# USART_LPUART.net
KiCad netlist of a schematic drawn in Altium Designer
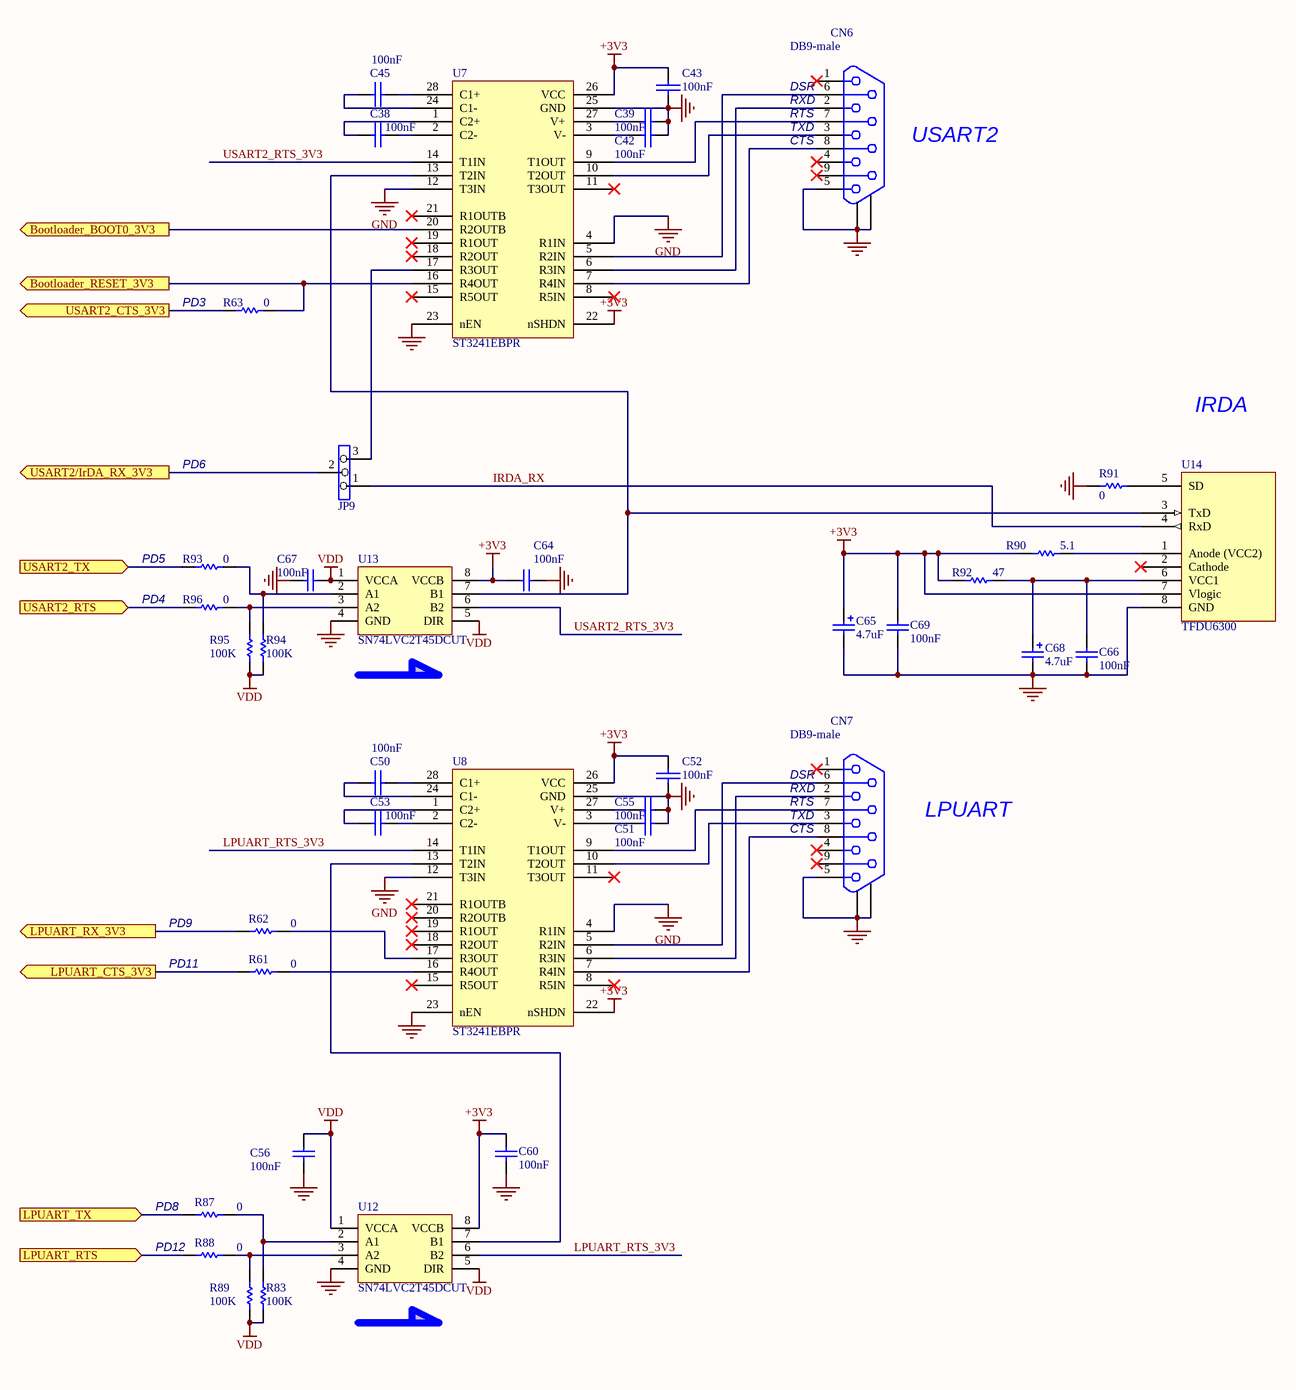
[diagram p0: USART_LPUART.SchDoc]

(export (version "E")
  (design (tool "Eeschema 10.0.6"))
  (components
    (comp (ref "C38")
      (value "100nF")
      (footprint "0402C")
      (description "Capacitor")
      (libsource (lib "*") (part "CAP"))
    )
    (comp (ref "C39")
      (value "100nF")
      (footprint "0402C")
      (description "Capacitor")
      (libsource (lib "*") (part "CAP"))
    )
    (comp (ref "C42")
      (value "100nF")
      (footprint "0402C")
      (description "Capacitor")
      (libsource (lib "*") (part "CAP"))
    )
    (comp (ref "C43")
      (value "100nF")
      (footprint "0402C")
      (description "Capacitor")
      (libsource (lib "*") (part "CAP"))
    )
    (comp (ref "C45")
      (value "100nF")
      (footprint "0402C")
      (description "Capacitor")
      (libsource (lib "*") (part "CAP"))
    )
    (comp (ref "C50")
      (value "100nF")
      (footprint "0402C")
      (description "Capacitor")
      (libsource (lib "*") (part "CAP"))
    )
    (comp (ref "C51")
      (value "100nF")
      (footprint "0402C")
      (description "Capacitor")
      (libsource (lib "*") (part "CAP"))
    )
    (comp (ref "C52")
      (value "100nF")
      (footprint "0402C")
      (description "Capacitor")
      (libsource (lib "*") (part "CAP"))
    )
    (comp (ref "C53")
      (value "100nF")
      (footprint "0402C")
      (description "Capacitor")
      (libsource (lib "*") (part "CAP"))
    )
    (comp (ref "C55")
      (value "100nF")
      (footprint "0402C")
      (description "Capacitor")
      (libsource (lib "*") (part "CAP"))
    )
    (comp (ref "C56")
      (value "100nF")
      (footprint "0402C")
      (description "Capacitor")
      (fields (field (name "PUBLISHER") "Altium Limited"))
      (libsource (lib "Miscellaneous Devices") (part "CAP"))
    )
    (comp (ref "C60")
      (value "100nF")
      (footprint "0402C")
      (description "Capacitor")
      (fields (field (name "PUBLISHER") "Altium Limited"))
      (libsource (lib "Miscellaneous Devices") (part "CAP"))
    )
    (comp (ref "C64")
      (value "100nF")
      (footprint "0402C")
      (description "Capacitor")
      (fields (field (name "PUBLISHER") "Altium Limited"))
      (libsource (lib "Miscellaneous Devices") (part "CAP"))
    )
    (comp (ref "C65")
      (value "4.7uF")
      (footprint "TAN-A")
      (description "Polarized Capacitor (Radial)")
      (fields (field (name "PUBLISHER") "Altium Limited"))
      (libsource (lib "Miscellaneous Devices") (part "Cap Pol1"))
    )
    (comp (ref "C66")
      (value "100nF")
      (footprint "0402C")
      (description "Capacitor")
      (fields (field (name "PUBLISHER") "Altium Limited"))
      (libsource (lib "Miscellaneous Devices") (part "CAP"))
    )
    (comp (ref "C67")
      (value "100nF")
      (footprint "0402C")
      (description "Capacitor")
      (fields (field (name "PUBLISHER") "Altium Limited"))
      (libsource (lib "Miscellaneous Devices") (part "CAP"))
    )
    (comp (ref "C68")
      (value "4.7uF")
      (footprint "TAN-A")
      (description "Polarized Capacitor (Radial)")
      (fields (field (name "PUBLISHER") "Altium Limited"))
      (libsource (lib "Miscellaneous Devices") (part "Cap Pol1"))
    )
    (comp (ref "C69")
      (value "100nF")
      (footprint "0402C")
      (description "Capacitor")
      (fields (field (name "PUBLISHER") "Altium Limited"))
      (libsource (lib "Miscellaneous Devices") (part "CAP"))
    )
    (comp (ref "CN6") (value "DB9-male") (footprint "DB9/M") (libsource (lib "MB1070") (part "DB9")))
    (comp (ref "CN7") (value "DB9-male") (footprint "DB9/M") (libsource (lib "MB1070") (part "DB9")))
    (comp (ref "JP9") (value "~") (footprint "SIP3") (libsource (lib "STR910_SCHLIB") (part "Jumper3")))
    (comp (ref "R61")
      (value "0")
      (footprint "0603R")
      (description "Resistor")
      (fields (field (name "PUBLISHER") "Altium Limited"))
      (libsource (lib "Miscellaneous Devices") (part "Res1"))
    )
    (comp (ref "R62")
      (value "0")
      (footprint "0603R")
      (description "Resistor")
      (fields (field (name "PUBLISHER") "Altium Limited"))
      (libsource (lib "Miscellaneous Devices") (part "Res1"))
    )
    (comp (ref "R63")
      (value "0")
      (footprint "0603R")
      (description "Resistor")
      (fields (field (name "PUBLISHER") "Altium Limited"))
      (libsource (lib "Miscellaneous Devices") (part "Res1"))
    )
    (comp (ref "R83")
      (value "100K")
      (footprint "0402R")
      (description "Resistor")
      (fields (field (name "PUBLISHER") "Altium Limited"))
      (libsource (lib "Miscellaneous Devices") (part "Res1"))
    )
    (comp (ref "R87")
      (value "0")
      (footprint "0603R")
      (description "Resistor")
      (fields (field (name "PUBLISHER") "Altium Limited"))
      (libsource (lib "Miscellaneous Devices") (part "Res1"))
    )
    (comp (ref "R88")
      (value "0")
      (footprint "0603R")
      (description "Resistor")
      (fields (field (name "PUBLISHER") "Altium Limited"))
      (libsource (lib "Miscellaneous Devices") (part "Res1"))
    )
    (comp (ref "R89")
      (value "100K")
      (footprint "0402R")
      (description "Resistor")
      (fields (field (name "PUBLISHER") "Altium Limited"))
      (libsource (lib "Miscellaneous Devices") (part "Res1"))
    )
    (comp (ref "R90")
      (value "5.1")
      (footprint "0402R")
      (description "Resistor")
      (fields (field (name "PUBLISHER") "Altium Limited"))
      (libsource (lib "Miscellaneous Devices") (part "Res1"))
    )
    (comp (ref "R91")
      (value "0")
      (footprint "0603R")
      (description "Resistor")
      (fields (field (name "PUBLISHER") "Altium Limited"))
      (libsource (lib "Miscellaneous Devices") (part "Res1"))
    )
    (comp (ref "R92")
      (value "47")
      (footprint "0402R")
      (description "Resistor")
      (fields (field (name "PUBLISHER") "Altium Limited"))
      (libsource (lib "Miscellaneous Devices") (part "Res1"))
    )
    (comp (ref "R93")
      (value "0")
      (footprint "0603R")
      (description "Resistor")
      (fields (field (name "PUBLISHER") "Altium Limited"))
      (libsource (lib "Miscellaneous Devices") (part "Res1"))
    )
    (comp (ref "R94")
      (value "100K")
      (footprint "0402R")
      (description "Resistor")
      (fields (field (name "PUBLISHER") "Altium Limited"))
      (libsource (lib "Miscellaneous Devices") (part "Res1"))
    )
    (comp (ref "R95")
      (value "100K")
      (footprint "0402R")
      (description "Resistor")
      (fields (field (name "PUBLISHER") "Altium Limited"))
      (libsource (lib "Miscellaneous Devices") (part "Res1"))
    )
    (comp (ref "R96")
      (value "0")
      (footprint "0603R")
      (description "Resistor")
      (fields (field (name "PUBLISHER") "Altium Limited"))
      (libsource (lib "Miscellaneous Devices") (part "Res1"))
    )
    (comp (ref "U7")
      (value "ST3241EBPR")
      (footprint "SSOP28_0R65_10R2X7R8")
      (libsource (lib "*") (part "ST3241"))
    )
    (comp (ref "U8")
      (value "ST3241EBPR")
      (footprint "SSOP28_0R65_10R2X7R8")
      (libsource (lib "*") (part "ST3241"))
    )
    (comp (ref "U12")
      (value "SN74LVC2T45DCUT")
      (footprint "USOP8_0R5_2X3R1")
      (libsource (lib "MB818") (part "SN74LVC2T45DCUT"))
    )
    (comp (ref "U13")
      (value "SN74LVC2T45DCUT")
      (footprint "USOP8_0R5_2X3R1")
      (libsource (lib "MB818") (part "SN74LVC2T45DCUT"))
    )
    (comp (ref "U14")
      (value "TFDU6300")
      (footprint "IR_VISHAY3")
      (description "TFDU4300")
      (libsource (lib "*") (part "TFDU4300"))
    )
  )
  (nets
    (net (code "1") (name "+3V3") (class "Default")
      (node (ref "C43") (pin "2") (pinfunction "2_2") (pintype "passive"))
      (node (ref "C52") (pin "2") (pinfunction "2_2") (pintype "passive"))
      (node (ref "C60") (pin "2") (pinfunction "2_2") (pintype "passive"))
      (node (ref "C64") (pin "2") (pinfunction "2_2") (pintype "passive"))
      (node (ref "C65") (pin "1") (pinfunction "1_1") (pintype "passive"))
      (node (ref "C69") (pin "2") (pinfunction "2_2") (pintype "passive"))
      (node (ref "R90") (pin "1") (pinfunction "1_1") (pintype "passive"))
      (node (ref "R92") (pin "1") (pinfunction "1_1") (pintype "passive"))
      (node (ref "U12") (pin "8") (pinfunction "VCCB_8") (pintype "passive"))
      (node (ref "U13") (pin "8") (pinfunction "VCCB_8") (pintype "passive"))
      (node (ref "U14") (pin "7") (pinfunction "Vlogic_7") (pintype "passive"))
      (node (ref "U7") (pin "22") (pinfunction "nSHDN_22") (pintype "passive"))
      (node (ref "U7") (pin "26") (pinfunction "VCC_26") (pintype "passive"))
      (node (ref "U8") (pin "22") (pinfunction "nSHDN_22") (pintype "passive"))
      (node (ref "U8") (pin "26") (pinfunction "VCC_26") (pintype "passive"))
    )
    (net (code "2") (name "/Bootloader_BOOT0_3V3") (class "Default")
      (node (ref "U7") (pin "20") (pinfunction "R2OUTB_20") (pintype "passive"))
    )
    (net (code "3") (name "/Bootloader_RESET_3V3") (class "Default")
      (node (ref "R63") (pin "1") (pinfunction "1_1") (pintype "passive"))
      (node (ref "U7") (pin "16") (pinfunction "R4OUT_16") (pintype "passive"))
    )
    (net (code "4") (name "/IRDA_RX") (class "Default")
      (node (ref "JP9") (pin "1") (pintype "passive"))
      (node (ref "U14") (pin "4") (pinfunction "RxD_4") (pintype "output"))
    )
    (net (code "5") (name "/LPUART_CTS_3V3") (class "Default")
      (node (ref "R61") (pin "1") (pinfunction "1_1") (pintype "passive"))
    )
    (net (code "6") (name "/LPUART_RTS") (class "Default")
      (node (ref "R88") (pin "1") (pinfunction "1_1") (pintype "passive"))
    )
    (net (code "7") (name "/LPUART_RTS_3V3") (class "Default")
      (node (ref "U12") (pin "6") (pinfunction "B2_6") (pintype "passive"))
      (node (ref "U8") (pin "14") (pinfunction "T1IN_14") (pintype "passive"))
    )
    (net (code "8") (name "/LPUART_RX_3V3") (class "Default")
      (node (ref "R62") (pin "1") (pinfunction "1_1") (pintype "passive"))
    )
    (net (code "9") (name "/LPUART_TX") (class "Default")
      (node (ref "R87") (pin "1") (pinfunction "1_1") (pintype "passive"))
    )
    (net (code "10") (name "/USART2_CTS_3V3") (class "Default")
      (node (ref "R63") (pin "2") (pinfunction "2_2") (pintype "passive"))
    )
    (net (code "11") (name "/USART2_RTS") (class "Default")
      (node (ref "R96") (pin "2") (pinfunction "2_2") (pintype "passive"))
    )
    (net (code "12") (name "/USART2_RTS_3V3") (class "Default")
      (node (ref "U13") (pin "6") (pinfunction "B2_6") (pintype "passive"))
      (node (ref "U7") (pin "14") (pinfunction "T1IN_14") (pintype "passive"))
    )
    (net (code "13") (name "/USART2_TX") (class "Default")
      (node (ref "R93") (pin "2") (pinfunction "2_2") (pintype "passive"))
    )
    (net (code "14") (name "/USART2{slash}IrDA_RX_3V3") (class "Default")
      (node (ref "JP9") (pin "2") (pintype "passive"))
    )
    (net (code "15") (name "GND") (class "Default")
      (node (ref "C39") (pin "2") (pinfunction "2_2") (pintype "passive"))
      (node (ref "C42") (pin "2") (pinfunction "2_2") (pintype "passive"))
      (node (ref "C43") (pin "1") (pinfunction "1_1") (pintype "passive"))
      (node (ref "C51") (pin "2") (pinfunction "2_2") (pintype "passive"))
      (node (ref "C52") (pin "1") (pinfunction "1_1") (pintype "passive"))
      (node (ref "C55") (pin "2") (pinfunction "2_2") (pintype "passive"))
      (node (ref "C56") (pin "1") (pinfunction "1_1") (pintype "passive"))
      (node (ref "C60") (pin "1") (pinfunction "1_1") (pintype "passive"))
      (node (ref "C64") (pin "1") (pinfunction "1_1") (pintype "passive"))
      (node (ref "C65") (pin "2") (pinfunction "2_2") (pintype "passive"))
      (node (ref "C66") (pin "1") (pinfunction "1_1") (pintype "passive"))
      (node (ref "C67") (pin "1") (pinfunction "1_1") (pintype "passive"))
      (node (ref "C68") (pin "2") (pinfunction "2_2") (pintype "passive"))
      (node (ref "C69") (pin "1") (pinfunction "1_1") (pintype "passive"))
      (node (ref "CN6") (pin "10") (pinfunction "10_10") (pintype "passive"))
      (node (ref "CN6") (pin "11") (pinfunction "11_11") (pintype "passive"))
      (node (ref "CN6") (pin "5") (pinfunction "5_5") (pintype "passive"))
      (node (ref "CN7") (pin "10") (pinfunction "10_10") (pintype "passive"))
      (node (ref "CN7") (pin "11") (pinfunction "11_11") (pintype "passive"))
      (node (ref "CN7") (pin "5") (pinfunction "5_5") (pintype "passive"))
      (node (ref "R91") (pin "2") (pinfunction "2_2") (pintype "passive"))
      (node (ref "U12") (pin "4") (pinfunction "GND_4") (pintype "passive"))
      (node (ref "U13") (pin "4") (pinfunction "GND_4") (pintype "passive"))
      (node (ref "U14") (pin "8") (pinfunction "GND_8") (pintype "passive"))
      (node (ref "U7") (pin "12") (pinfunction "T3IN_12") (pintype "passive"))
      (node (ref "U7") (pin "23") (pinfunction "nEN_23") (pintype "passive"))
      (node (ref "U7") (pin "25") (pinfunction "GND_25") (pintype "passive"))
      (node (ref "U7") (pin "4") (pinfunction "R1IN_4") (pintype "passive"))
      (node (ref "U8") (pin "12") (pinfunction "T3IN_12") (pintype "passive"))
      (node (ref "U8") (pin "23") (pinfunction "nEN_23") (pintype "passive"))
      (node (ref "U8") (pin "25") (pinfunction "GND_25") (pintype "passive"))
      (node (ref "U8") (pin "4") (pinfunction "R1IN_4") (pintype "passive"))
    )
    (net (code "16") (name "Net-(U7-C1+)") (class "Default")
      (node (ref "C45") (pin "2") (pinfunction "2_2") (pintype "passive"))
      (node (ref "U7") (pin "28") (pinfunction "C1+_28") (pintype "passive"))
    )
    (net (code "17") (name "Net-(U7-C1-)") (class "Default")
      (node (ref "C45") (pin "1") (pinfunction "1_1") (pintype "passive"))
      (node (ref "U7") (pin "24") (pinfunction "C1-_24") (pintype "passive"))
    )
    (net (code "18") (name "Net-(U7-C2+)") (class "Default")
      (node (ref "C38") (pin "1") (pinfunction "1_1") (pintype "passive"))
      (node (ref "U7") (pin "1") (pinfunction "C2+_1") (pintype "passive"))
    )
    (net (code "19") (name "Net-(U7-C2-)") (class "Default")
      (node (ref "C38") (pin "2") (pinfunction "2_2") (pintype "passive"))
      (node (ref "U7") (pin "2") (pinfunction "C2-_2") (pintype "passive"))
    )
    (net (code "20") (name "Net-(U7-R2IN)") (class "Default")
      (node (ref "CN6") (pin "6") (pinfunction "6_6") (pintype "passive"))
      (node (ref "U7") (pin "5") (pinfunction "R2IN_5") (pintype "passive"))
    )
    (net (code "21") (name "Net-(U7-R3IN)") (class "Default")
      (node (ref "CN6") (pin "2") (pinfunction "2_2") (pintype "passive"))
      (node (ref "U7") (pin "6") (pinfunction "R3IN_6") (pintype "passive"))
    )
    (net (code "22") (name "Net-(U7-R3OUT)") (class "Default")
      (node (ref "JP9") (pin "3") (pintype "passive"))
      (node (ref "U7") (pin "17") (pinfunction "R3OUT_17") (pintype "passive"))
    )
    (net (code "23") (name "Net-(U7-R4IN)") (class "Default")
      (node (ref "CN6") (pin "8") (pinfunction "8_8") (pintype "passive"))
      (node (ref "U7") (pin "7") (pinfunction "R4IN_7") (pintype "passive"))
    )
    (net (code "24") (name "Net-(U7-T1OUT)") (class "Default")
      (node (ref "CN6") (pin "7") (pinfunction "7_7") (pintype "passive"))
      (node (ref "U7") (pin "9") (pinfunction "T1OUT_9") (pintype "passive"))
    )
    (net (code "25") (name "Net-(U7-T2OUT)") (class "Default")
      (node (ref "CN6") (pin "3") (pinfunction "3_3") (pintype "passive"))
      (node (ref "U7") (pin "10") (pinfunction "T2OUT_10") (pintype "passive"))
    )
    (net (code "26") (name "Net-(U7-V+)") (class "Default")
      (node (ref "C39") (pin "1") (pinfunction "1_1") (pintype "passive"))
      (node (ref "U7") (pin "27") (pinfunction "V+_27") (pintype "passive"))
    )
    (net (code "27") (name "Net-(U7-V-)") (class "Default")
      (node (ref "C42") (pin "1") (pinfunction "1_1") (pintype "passive"))
      (node (ref "U7") (pin "3") (pinfunction "V-_3") (pintype "passive"))
    )
    (net (code "28") (name "Net-(U8-C1+)") (class "Default")
      (node (ref "C50") (pin "2") (pinfunction "2_2") (pintype "passive"))
      (node (ref "U8") (pin "28") (pinfunction "C1+_28") (pintype "passive"))
    )
    (net (code "29") (name "Net-(U8-C1-)") (class "Default")
      (node (ref "C50") (pin "1") (pinfunction "1_1") (pintype "passive"))
      (node (ref "U8") (pin "24") (pinfunction "C1-_24") (pintype "passive"))
    )
    (net (code "30") (name "Net-(U8-C2+)") (class "Default")
      (node (ref "C53") (pin "1") (pinfunction "1_1") (pintype "passive"))
      (node (ref "U8") (pin "1") (pinfunction "C2+_1") (pintype "passive"))
    )
    (net (code "31") (name "Net-(U8-C2-)") (class "Default")
      (node (ref "C53") (pin "2") (pinfunction "2_2") (pintype "passive"))
      (node (ref "U8") (pin "2") (pinfunction "C2-_2") (pintype "passive"))
    )
    (net (code "32") (name "Net-(U8-R2IN)") (class "Default")
      (node (ref "CN7") (pin "6") (pinfunction "6_6") (pintype "passive"))
      (node (ref "U8") (pin "5") (pinfunction "R2IN_5") (pintype "passive"))
    )
    (net (code "33") (name "Net-(U8-R3IN)") (class "Default")
      (node (ref "CN7") (pin "2") (pinfunction "2_2") (pintype "passive"))
      (node (ref "U8") (pin "6") (pinfunction "R3IN_6") (pintype "passive"))
    )
    (net (code "34") (name "Net-(U8-R3OUT)") (class "Default")
      (node (ref "R62") (pin "2") (pinfunction "2_2") (pintype "passive"))
      (node (ref "U8") (pin "17") (pinfunction "R3OUT_17") (pintype "passive"))
    )
    (net (code "35") (name "Net-(U8-R4IN)") (class "Default")
      (node (ref "CN7") (pin "8") (pinfunction "8_8") (pintype "passive"))
      (node (ref "U8") (pin "7") (pinfunction "R4IN_7") (pintype "passive"))
    )
    (net (code "36") (name "Net-(U8-R4OUT)") (class "Default")
      (node (ref "R61") (pin "2") (pinfunction "2_2") (pintype "passive"))
      (node (ref "U8") (pin "16") (pinfunction "R4OUT_16") (pintype "passive"))
    )
    (net (code "37") (name "Net-(U8-T1OUT)") (class "Default")
      (node (ref "CN7") (pin "7") (pinfunction "7_7") (pintype "passive"))
      (node (ref "U8") (pin "9") (pinfunction "T1OUT_9") (pintype "passive"))
    )
    (net (code "38") (name "Net-(U8-T2OUT)") (class "Default")
      (node (ref "CN7") (pin "3") (pinfunction "3_3") (pintype "passive"))
      (node (ref "U8") (pin "10") (pinfunction "T2OUT_10") (pintype "passive"))
    )
    (net (code "39") (name "Net-(U8-V+)") (class "Default")
      (node (ref "C55") (pin "1") (pinfunction "1_1") (pintype "passive"))
      (node (ref "U8") (pin "27") (pinfunction "V+_27") (pintype "passive"))
    )
    (net (code "40") (name "Net-(U8-V-)") (class "Default")
      (node (ref "C51") (pin "1") (pinfunction "1_1") (pintype "passive"))
      (node (ref "U8") (pin "3") (pinfunction "V-_3") (pintype "passive"))
    )
    (net (code "41") (name "Net-(U12-A1)") (class "Default")
      (node (ref "R83") (pin "1") (pinfunction "1_1") (pintype "passive"))
      (node (ref "R87") (pin "2") (pinfunction "2_2") (pintype "passive"))
      (node (ref "U12") (pin "2") (pinfunction "A1_2") (pintype "passive"))
    )
    (net (code "42") (name "Net-(U12-A2)") (class "Default")
      (node (ref "R88") (pin "2") (pinfunction "2_2") (pintype "passive"))
      (node (ref "R89") (pin "1") (pinfunction "1_1") (pintype "passive"))
      (node (ref "U12") (pin "3") (pinfunction "A2_3") (pintype "passive"))
    )
    (net (code "43") (name "Net-(U12-B1)") (class "Default")
      (node (ref "U12") (pin "7") (pinfunction "B1_7") (pintype "passive"))
      (node (ref "U8") (pin "13") (pinfunction "T2IN_13") (pintype "passive"))
    )
    (net (code "44") (name "Net-(U13-A1)") (class "Default")
      (node (ref "R93") (pin "1") (pinfunction "1_1") (pintype "passive"))
      (node (ref "R94") (pin "1") (pinfunction "1_1") (pintype "passive"))
      (node (ref "U13") (pin "2") (pinfunction "A1_2") (pintype "passive"))
    )
    (net (code "45") (name "Net-(U13-A2)") (class "Default")
      (node (ref "R95") (pin "1") (pinfunction "1_1") (pintype "passive"))
      (node (ref "R96") (pin "1") (pinfunction "1_1") (pintype "passive"))
      (node (ref "U13") (pin "3") (pinfunction "A2_3") (pintype "passive"))
    )
    (net (code "46") (name "Net-(U13-B1)") (class "Default")
      (node (ref "U13") (pin "7") (pinfunction "B1_7") (pintype "passive"))
      (node (ref "U14") (pin "3") (pinfunction "TxD_3") (pintype "input"))
      (node (ref "U7") (pin "13") (pinfunction "T2IN_13") (pintype "passive"))
    )
    (net (code "47") (name "Net-(U14-Anode_(VCC2))") (class "Default")
      (node (ref "R90") (pin "2") (pinfunction "2_2") (pintype "passive"))
      (node (ref "U14") (pin "1") (pinfunction "Anode_(VCC2)_1") (pintype "passive"))
    )
    (net (code "48") (name "Net-(U14-SD)") (class "Default")
      (node (ref "R91") (pin "1") (pinfunction "1_1") (pintype "passive"))
      (node (ref "U14") (pin "5") (pinfunction "SD_5") (pintype "passive"))
    )
    (net (code "49") (name "Net-(U14-VCC1)") (class "Default")
      (node (ref "C66") (pin "2") (pinfunction "2_2") (pintype "passive"))
      (node (ref "C68") (pin "1") (pinfunction "1_1") (pintype "passive"))
      (node (ref "R92") (pin "2") (pinfunction "2_2") (pintype "passive"))
      (node (ref "U14") (pin "6") (pinfunction "VCC1_6") (pintype "passive"))
    )
    (net (code "50") (name "VDD") (class "Default")
      (node (ref "C56") (pin "2") (pinfunction "2_2") (pintype "passive"))
      (node (ref "C67") (pin "2") (pinfunction "2_2") (pintype "passive"))
      (node (ref "R83") (pin "2") (pinfunction "2_2") (pintype "passive"))
      (node (ref "R89") (pin "2") (pinfunction "2_2") (pintype "passive"))
      (node (ref "R94") (pin "2") (pinfunction "2_2") (pintype "passive"))
      (node (ref "R95") (pin "2") (pinfunction "2_2") (pintype "passive"))
      (node (ref "U12") (pin "1") (pinfunction "VCCA_1") (pintype "passive"))
      (node (ref "U12") (pin "5") (pinfunction "DIR_5") (pintype "passive"))
      (node (ref "U13") (pin "1") (pinfunction "VCCA_1") (pintype "passive"))
      (node (ref "U13") (pin "5") (pinfunction "DIR_5") (pintype "passive"))
    )
    (net (code "51") (name "unconnected-(CN6-Pad1)") (class "Default")
      (node (ref "CN6") (pin "1") (pinfunction "1_1") (pintype "passive+no_connect"))
    )
    (net (code "52") (name "unconnected-(CN6-Pad4)") (class "Default")
      (node (ref "CN6") (pin "4") (pinfunction "4_4") (pintype "passive+no_connect"))
    )
    (net (code "53") (name "unconnected-(CN6-Pad9)") (class "Default")
      (node (ref "CN6") (pin "9") (pinfunction "9_9") (pintype "passive+no_connect"))
    )
    (net (code "54") (name "unconnected-(CN7-Pad1)") (class "Default")
      (node (ref "CN7") (pin "1") (pinfunction "1_1") (pintype "passive+no_connect"))
    )
    (net (code "55") (name "unconnected-(CN7-Pad4)") (class "Default")
      (node (ref "CN7") (pin "4") (pinfunction "4_4") (pintype "passive+no_connect"))
    )
    (net (code "56") (name "unconnected-(CN7-Pad9)") (class "Default")
      (node (ref "CN7") (pin "9") (pinfunction "9_9") (pintype "passive+no_connect"))
    )
    (net (code "57") (name "unconnected-(U7-R1OUT-Pad19)") (class "Default")
      (node (ref "U7") (pin "19") (pinfunction "R1OUT_19") (pintype "passive+no_connect"))
    )
    (net (code "58") (name "unconnected-(U7-R1OUTB-Pad21)") (class "Default")
      (node (ref "U7") (pin "21") (pinfunction "R1OUTB_21") (pintype "passive+no_connect"))
    )
    (net (code "59") (name "unconnected-(U7-R2OUT-Pad18)") (class "Default")
      (node (ref "U7") (pin "18") (pinfunction "R2OUT_18") (pintype "passive+no_connect"))
    )
    (net (code "60") (name "unconnected-(U7-R5IN-Pad8)") (class "Default")
      (node (ref "U7") (pin "8") (pinfunction "R5IN_8") (pintype "passive+no_connect"))
    )
    (net (code "61") (name "unconnected-(U7-R5OUT-Pad15)") (class "Default")
      (node (ref "U7") (pin "15") (pinfunction "R5OUT_15") (pintype "passive+no_connect"))
    )
    (net (code "62") (name "unconnected-(U7-T3OUT-Pad11)") (class "Default")
      (node (ref "U7") (pin "11") (pinfunction "T3OUT_11") (pintype "passive+no_connect"))
    )
    (net (code "63") (name "unconnected-(U8-R1OUT-Pad19)") (class "Default")
      (node (ref "U8") (pin "19") (pinfunction "R1OUT_19") (pintype "passive+no_connect"))
    )
    (net (code "64") (name "unconnected-(U8-R1OUTB-Pad21)") (class "Default")
      (node (ref "U8") (pin "21") (pinfunction "R1OUTB_21") (pintype "passive+no_connect"))
    )
    (net (code "65") (name "unconnected-(U8-R2OUT-Pad18)") (class "Default")
      (node (ref "U8") (pin "18") (pinfunction "R2OUT_18") (pintype "passive+no_connect"))
    )
    (net (code "66") (name "unconnected-(U8-R2OUTB-Pad20)") (class "Default")
      (node (ref "U8") (pin "20") (pinfunction "R2OUTB_20") (pintype "passive+no_connect"))
    )
    (net (code "67") (name "unconnected-(U8-R5IN-Pad8)") (class "Default")
      (node (ref "U8") (pin "8") (pinfunction "R5IN_8") (pintype "passive+no_connect"))
    )
    (net (code "68") (name "unconnected-(U8-R5OUT-Pad15)") (class "Default")
      (node (ref "U8") (pin "15") (pinfunction "R5OUT_15") (pintype "passive+no_connect"))
    )
    (net (code "69") (name "unconnected-(U8-T3OUT-Pad11)") (class "Default")
      (node (ref "U8") (pin "11") (pinfunction "T3OUT_11") (pintype "passive+no_connect"))
    )
    (net (code "70") (name "unconnected-(U14-Cathode-Pad2)") (class "Default")
      (node (ref "U14") (pin "2") (pinfunction "Cathode_2") (pintype "passive+no_connect"))
    )
  )
)
